# SchematicTest.net
KiCad netlist of a schematic drawn in EAGLE
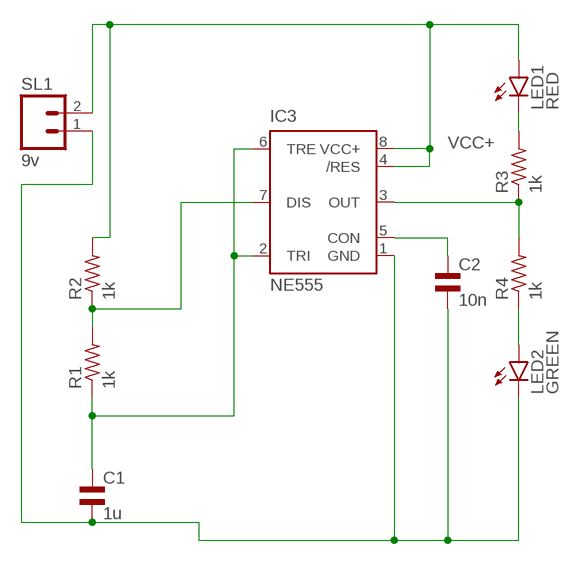
[diagram p0: schematic, sheet 1]

(export (version "E")
  (design (tool "Eeschema 10.0.6"))
  (components
    (comp (ref "C1")
      (value "1u")
      (footprint "eagle-import:EU25-10")
      (libsource (lib "eagle-import") (part "EL-BI25-10AXIAL"))
    )
    (comp (ref "C2")
      (value "10n")
      (footprint "eagle-import:EU25-10")
      (libsource (lib "eagle-import") (part "EL-BI25-10AXIAL"))
    )
    (comp (ref "IC3")
      (value "NE555")
      (footprint "eagle-import:DIL-08")
      (fields (field (name "MF") "Arrow Electronics") (field (name "MPN") "NE555N"))
      (libsource (lib "eagle-import") (part "NE555"))
    )
    (comp (ref "LED1")
      (value "RED")
      (footprint "eagle-import:LED5MM")
      (libsource (lib "eagle-import") (part "LED5MM"))
    )
    (comp (ref "LED2")
      (value "GREEN")
      (footprint "eagle-import:LED5MM")
      (libsource (lib "eagle-import") (part "LED5MM"))
    )
    (comp (ref "R1")
      (value "1k")
      (footprint "eagle-import:0204V")
      (libsource (lib "eagle-import") (part "R-US_0204/2V"))
    )
    (comp (ref "R2")
      (value "1k")
      (footprint "eagle-import:0204V")
      (libsource (lib "eagle-import") (part "R-US_0204/2V"))
    )
    (comp (ref "R3")
      (value "1k")
      (footprint "eagle-import:0204V")
      (libsource (lib "eagle-import") (part "R-US_0204/2V"))
    )
    (comp (ref "R4")
      (value "1k")
      (footprint "eagle-import:0204V")
      (libsource (lib "eagle-import") (part "R-US_0204/2V"))
    )
    (comp (ref "SL1")
      (value "9v")
      (footprint "eagle-import:02P")
      (libsource (lib "eagle-import") (part "M02"))
    )
  )
  (nets
    (net (code "1") (name "/VCC+") (class "Default")
      (node (ref "IC3") (pin "4") (pinfunction "/RES_4") (pintype "input"))
      (node (ref "IC3") (pin "8") (pinfunction "VCC+_8") (pintype "power_in"))
      (node (ref "LED1") (pin "A") (pinfunction "A_A") (pintype "passive"))
      (node (ref "R2") (pin "2") (pinfunction "2_2") (pintype "passive"))
      (node (ref "SL1") (pin "2") (pinfunction "2_2") (pintype "passive"))
    )
    (net (code "2") (name "Net-(IC3-CON)") (class "Default")
      (node (ref "C2") (pin "1") (pinfunction "1_1") (pintype "passive"))
      (node (ref "IC3") (pin "5") (pinfunction "CON_5") (pintype "input"))
    )
    (net (code "3") (name "Net-(IC3-DIS)") (class "Default")
      (node (ref "IC3") (pin "7") (pinfunction "DIS_7") (pintype "input"))
      (node (ref "R1") (pin "2") (pinfunction "2_2") (pintype "passive"))
      (node (ref "R2") (pin "1") (pinfunction "1_1") (pintype "passive"))
    )
    (net (code "4") (name "Net-(IC3-GND)") (class "Default")
      (node (ref "C1") (pin "2") (pinfunction "2_2") (pintype "passive"))
      (node (ref "C2") (pin "2") (pinfunction "2_2") (pintype "passive"))
      (node (ref "IC3") (pin "1") (pinfunction "GND_1") (pintype "power_in"))
      (node (ref "LED2") (pin "K") (pinfunction "C_K") (pintype "passive"))
      (node (ref "SL1") (pin "1") (pinfunction "1_1") (pintype "passive"))
    )
    (net (code "5") (name "Net-(IC3-OUT)") (class "Default")
      (node (ref "IC3") (pin "3") (pinfunction "OUT_3") (pintype "output"))
      (node (ref "R3") (pin "1") (pinfunction "1_1") (pintype "passive"))
      (node (ref "R4") (pin "2") (pinfunction "2_2") (pintype "passive"))
    )
    (net (code "6") (name "Net-(IC3-TRE)") (class "Default")
      (node (ref "C1") (pin "1") (pinfunction "1_1") (pintype "passive"))
      (node (ref "IC3") (pin "2") (pinfunction "TRI_2") (pintype "input"))
      (node (ref "IC3") (pin "6") (pinfunction "TRE_6") (pintype "input"))
      (node (ref "R1") (pin "1") (pinfunction "1_1") (pintype "passive"))
    )
    (net (code "7") (name "Net-(LED1-C)") (class "Default")
      (node (ref "LED1") (pin "K") (pinfunction "C_K") (pintype "passive"))
      (node (ref "R3") (pin "2") (pinfunction "2_2") (pintype "passive"))
    )
    (net (code "8") (name "Net-(LED2-PadA)") (class "Default")
      (node (ref "LED2") (pin "A") (pinfunction "A_A") (pintype "passive"))
      (node (ref "R4") (pin "1") (pinfunction "1_1") (pintype "passive"))
    )
  )
)
